# tick-display-mk-3_1.net
KiCad netlist of a schematic drawn in EAGLE
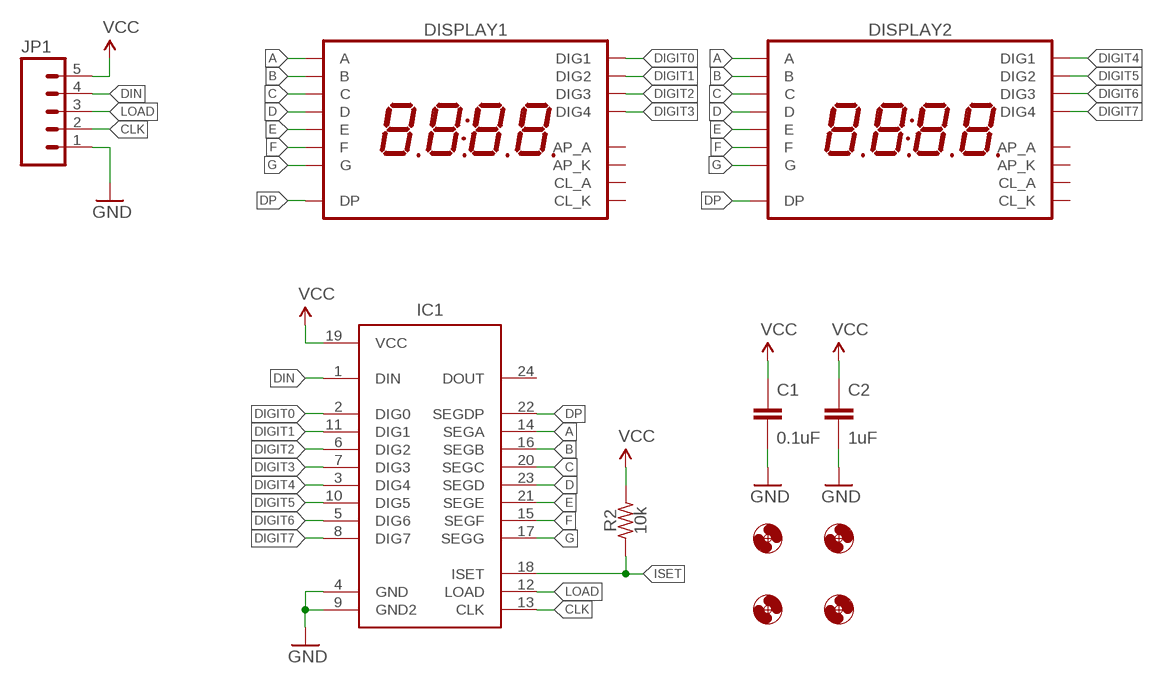
[diagram p0: schematic, sheet 1]

(export (version "E")
  (design (tool "Eeschema 10.0.6"))
  (components
    (comp (ref "C1")
      (value "0.1uF")
      (footprint "eagle-import:C025-024X044")
      (libsource (lib "eagle-import") (part "CAPACITOR-CERAMIC025-024X044"))
    )
    (comp (ref "C2")
      (value "1uF")
      (footprint "eagle-import:C025-024X044")
      (libsource (lib "eagle-import") (part "CAPACITOR-CERAMIC025-024X044"))
    )
    (comp (ref "DISPLAY1")
      (value "7SEG_4DIGIT_10MM")
      (footprint "eagle-import:7SEG_4DIG_10MM")
      (libsource (lib "eagle-import") (part "7SEG_4DIGIT_10MM"))
    )
    (comp (ref "DISPLAY2")
      (value "7SEG_4DIGIT_10MM")
      (footprint "eagle-import:7SEG_4DIG_10MM")
      (libsource (lib "eagle-import") (part "7SEG_4DIGIT_10MM"))
    )
    (comp (ref "H1")
      (value "HOLE#2")
      (footprint "eagle-import:HOLE-#2")
      (libsource (lib "eagle-import") (part "HOLE#2"))
    )
    (comp (ref "H2")
      (value "HOLE#2")
      (footprint "eagle-import:HOLE-#2")
      (libsource (lib "eagle-import") (part "HOLE#2"))
    )
    (comp (ref "H3")
      (value "HOLE#2")
      (footprint "eagle-import:HOLE-#2")
      (libsource (lib "eagle-import") (part "HOLE#2"))
    )
    (comp (ref "H4")
      (value "HOLE#2")
      (footprint "eagle-import:HOLE-#2")
      (libsource (lib "eagle-import") (part "HOLE#2"))
    )
    (comp (ref "IC1")
      (value "MAX7219CWG")
      (footprint "eagle-import:SO24W")
      (libsource (lib "eagle-import") (part "MAX7219SOIC-W"))
    )
    (comp (ref "JP1")
      (value "M05PTH")
      (footprint "eagle-import:1X05")
      (libsource (lib "eagle-import") (part "M05PTH"))
    )
    (comp (ref "R2")
      (value "10k")
      (footprint "eagle-import:RESISTOR-AXIAL-PTH-5.08MM")
      (libsource (lib "eagle-import") (part "RESISTORPTH-AXIAL-5.08MM"))
    )
  )
  (nets
    (net (code "1") (name "A") (class "Default")
      (node (ref "DISPLAY1") (pin "14") (pinfunction "A_14") (pintype "passive"))
      (node (ref "DISPLAY2") (pin "14") (pinfunction "A_14") (pintype "passive"))
      (node (ref "IC1") (pin "14") (pinfunction "SEGA_14") (pintype "bidirectional"))
    )
    (net (code "2") (name "B") (class "Default")
      (node (ref "DISPLAY1") (pin "16") (pinfunction "B_16") (pintype "passive"))
      (node (ref "DISPLAY2") (pin "16") (pinfunction "B_16") (pintype "passive"))
      (node (ref "IC1") (pin "16") (pinfunction "SEGB_16") (pintype "bidirectional"))
    )
    (net (code "3") (name "C") (class "Default")
      (node (ref "DISPLAY1") (pin "13") (pinfunction "C_13") (pintype "passive"))
      (node (ref "DISPLAY2") (pin "13") (pinfunction "C_13") (pintype "passive"))
      (node (ref "IC1") (pin "20") (pinfunction "SEGC_20") (pintype "bidirectional"))
    )
    (net (code "4") (name "CLK") (class "Default")
      (node (ref "IC1") (pin "13") (pinfunction "CLK_13") (pintype "bidirectional"))
      (node (ref "JP1") (pin "2") (pinfunction "2_2") (pintype "passive"))
    )
    (net (code "5") (name "D") (class "Default")
      (node (ref "DISPLAY1") (pin "3") (pinfunction "D_3") (pintype "passive"))
      (node (ref "DISPLAY2") (pin "3") (pinfunction "D_3") (pintype "passive"))
      (node (ref "IC1") (pin "23") (pinfunction "SEGD_23") (pintype "bidirectional"))
    )
    (net (code "6") (name "DIGIT0") (class "Default")
      (node (ref "DISPLAY1") (pin "1") (pinfunction "DIG1_1") (pintype "passive"))
      (node (ref "IC1") (pin "2") (pinfunction "DIG0_2") (pintype "bidirectional"))
    )
    (net (code "7") (name "DIGIT1") (class "Default")
      (node (ref "DISPLAY1") (pin "2") (pinfunction "DIG2_2") (pintype "passive"))
      (node (ref "IC1") (pin "11") (pinfunction "DIG1_11") (pintype "bidirectional"))
    )
    (net (code "8") (name "DIGIT2") (class "Default")
      (node (ref "DISPLAY1") (pin "6") (pinfunction "DIG3_6") (pintype "passive"))
      (node (ref "IC1") (pin "6") (pinfunction "DIG2_6") (pintype "bidirectional"))
    )
    (net (code "9") (name "DIGIT3") (class "Default")
      (node (ref "DISPLAY1") (pin "8") (pinfunction "DIG4_8") (pintype "passive"))
      (node (ref "IC1") (pin "7") (pinfunction "DIG3_7") (pintype "bidirectional"))
    )
    (net (code "10") (name "DIGIT4") (class "Default")
      (node (ref "DISPLAY2") (pin "1") (pinfunction "DIG1_1") (pintype "passive"))
      (node (ref "IC1") (pin "3") (pinfunction "DIG4_3") (pintype "bidirectional"))
    )
    (net (code "11") (name "DIGIT5") (class "Default")
      (node (ref "DISPLAY2") (pin "2") (pinfunction "DIG2_2") (pintype "passive"))
      (node (ref "IC1") (pin "10") (pinfunction "DIG5_10") (pintype "bidirectional"))
    )
    (net (code "12") (name "DIGIT6") (class "Default")
      (node (ref "DISPLAY2") (pin "6") (pinfunction "DIG3_6") (pintype "passive"))
      (node (ref "IC1") (pin "5") (pinfunction "DIG6_5") (pintype "bidirectional"))
    )
    (net (code "13") (name "DIGIT7") (class "Default")
      (node (ref "DISPLAY2") (pin "8") (pinfunction "DIG4_8") (pintype "passive"))
      (node (ref "IC1") (pin "8") (pinfunction "DIG7_8") (pintype "bidirectional"))
    )
    (net (code "14") (name "DIN") (class "Default")
      (node (ref "IC1") (pin "1") (pinfunction "DIN_1") (pintype "bidirectional"))
      (node (ref "JP1") (pin "4") (pinfunction "4_4") (pintype "passive"))
    )
    (net (code "15") (name "DP") (class "Default")
      (node (ref "DISPLAY1") (pin "7") (pinfunction "DP_7") (pintype "passive"))
      (node (ref "DISPLAY2") (pin "7") (pinfunction "DP_7") (pintype "passive"))
      (node (ref "IC1") (pin "22") (pinfunction "SEGDP_22") (pintype "bidirectional"))
    )
    (net (code "16") (name "E") (class "Default")
      (node (ref "DISPLAY1") (pin "5") (pinfunction "E_5") (pintype "passive"))
      (node (ref "DISPLAY2") (pin "5") (pinfunction "E_5") (pintype "passive"))
      (node (ref "IC1") (pin "21") (pinfunction "SEGE_21") (pintype "bidirectional"))
    )
    (net (code "17") (name "F") (class "Default")
      (node (ref "DISPLAY1") (pin "11") (pinfunction "F_11") (pintype "passive"))
      (node (ref "DISPLAY2") (pin "11") (pinfunction "F_11") (pintype "passive"))
      (node (ref "IC1") (pin "15") (pinfunction "SEGF_15") (pintype "bidirectional"))
    )
    (net (code "18") (name "G") (class "Default")
      (node (ref "DISPLAY1") (pin "15") (pinfunction "G_15") (pintype "passive"))
      (node (ref "DISPLAY2") (pin "15") (pinfunction "G_15") (pintype "passive"))
      (node (ref "IC1") (pin "17") (pinfunction "SEGG_17") (pintype "bidirectional"))
    )
    (net (code "19") (name "GND") (class "Default")
      (node (ref "C1") (pin "2") (pinfunction "2_2") (pintype "passive"))
      (node (ref "C2") (pin "2") (pinfunction "2_2") (pintype "passive"))
      (node (ref "IC1") (pin "4") (pinfunction "GND_4") (pintype "bidirectional"))
      (node (ref "IC1") (pin "9") (pinfunction "GND2_9") (pintype "bidirectional"))
      (node (ref "JP1") (pin "1") (pinfunction "1_1") (pintype "passive"))
    )
    (net (code "20") (name "ISET") (class "Default")
      (node (ref "IC1") (pin "18") (pinfunction "ISET_18") (pintype "bidirectional"))
      (node (ref "R2") (pin "P$1") (pinfunction "1_P$1") (pintype "passive"))
    )
    (net (code "21") (name "LOAD") (class "Default")
      (node (ref "IC1") (pin "12") (pinfunction "LOAD_12") (pintype "bidirectional"))
      (node (ref "JP1") (pin "3") (pinfunction "3_3") (pintype "passive"))
    )
    (net (code "22") (name "VCC") (class "Default")
      (node (ref "C1") (pin "1") (pinfunction "1_1") (pintype "passive"))
      (node (ref "C2") (pin "1") (pinfunction "1_1") (pintype "passive"))
      (node (ref "IC1") (pin "19") (pinfunction "VCC_19") (pintype "bidirectional"))
      (node (ref "JP1") (pin "5") (pinfunction "5_5") (pintype "passive"))
      (node (ref "R2") (pin "P$2") (pinfunction "2_P$2") (pintype "passive"))
    )
    (net (code "23") (name "unconnected-(DISPLAY1-AP_A-Pad10)") (class "Default")
      (node (ref "DISPLAY1") (pin "10") (pinfunction "AP_A_10") (pintype "bidirectional"))
    )
    (net (code "24") (name "unconnected-(DISPLAY1-AP_K-Pad9)") (class "Default")
      (node (ref "DISPLAY1") (pin "9") (pinfunction "AP_K_9") (pintype "bidirectional"))
    )
    (net (code "25") (name "unconnected-(DISPLAY1-CL_A-Pad4)") (class "Default")
      (node (ref "DISPLAY1") (pin "4") (pinfunction "CL_A_4") (pintype "passive"))
    )
    (net (code "26") (name "unconnected-(DISPLAY1-CL_K-Pad12)") (class "Default")
      (node (ref "DISPLAY1") (pin "12") (pinfunction "CL_K_12") (pintype "passive"))
    )
    (net (code "27") (name "unconnected-(DISPLAY2-AP_A-Pad10)") (class "Default")
      (node (ref "DISPLAY2") (pin "10") (pinfunction "AP_A_10") (pintype "bidirectional"))
    )
    (net (code "28") (name "unconnected-(DISPLAY2-AP_K-Pad9)") (class "Default")
      (node (ref "DISPLAY2") (pin "9") (pinfunction "AP_K_9") (pintype "bidirectional"))
    )
    (net (code "29") (name "unconnected-(DISPLAY2-CL_A-Pad4)") (class "Default")
      (node (ref "DISPLAY2") (pin "4") (pinfunction "CL_A_4") (pintype "passive"))
    )
    (net (code "30") (name "unconnected-(DISPLAY2-CL_K-Pad12)") (class "Default")
      (node (ref "DISPLAY2") (pin "12") (pinfunction "CL_K_12") (pintype "passive"))
    )
    (net (code "31") (name "unconnected-(IC1-DOUT-Pad24)") (class "Default")
      (node (ref "IC1") (pin "24") (pinfunction "DOUT_24") (pintype "bidirectional"))
    )
  )
)
